# MainBoard.net
KiCad netlist of a schematic drawn in Altium Designer
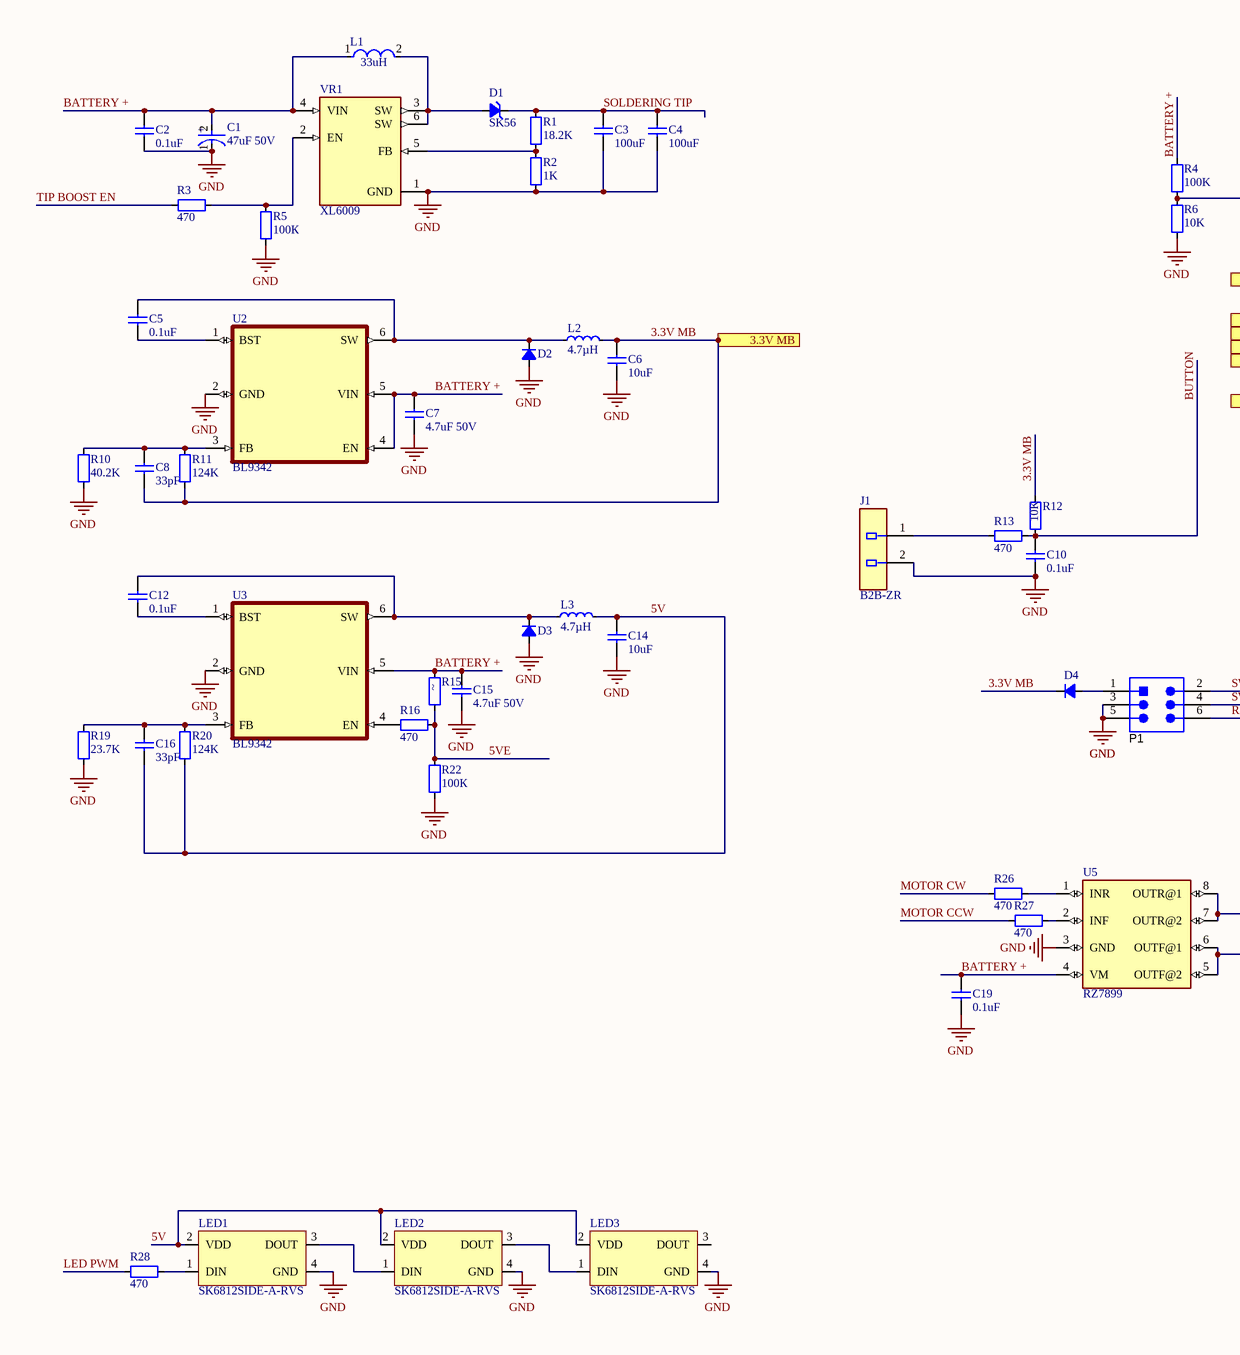
[diagram p0: MainBoard.SchDoc, left]
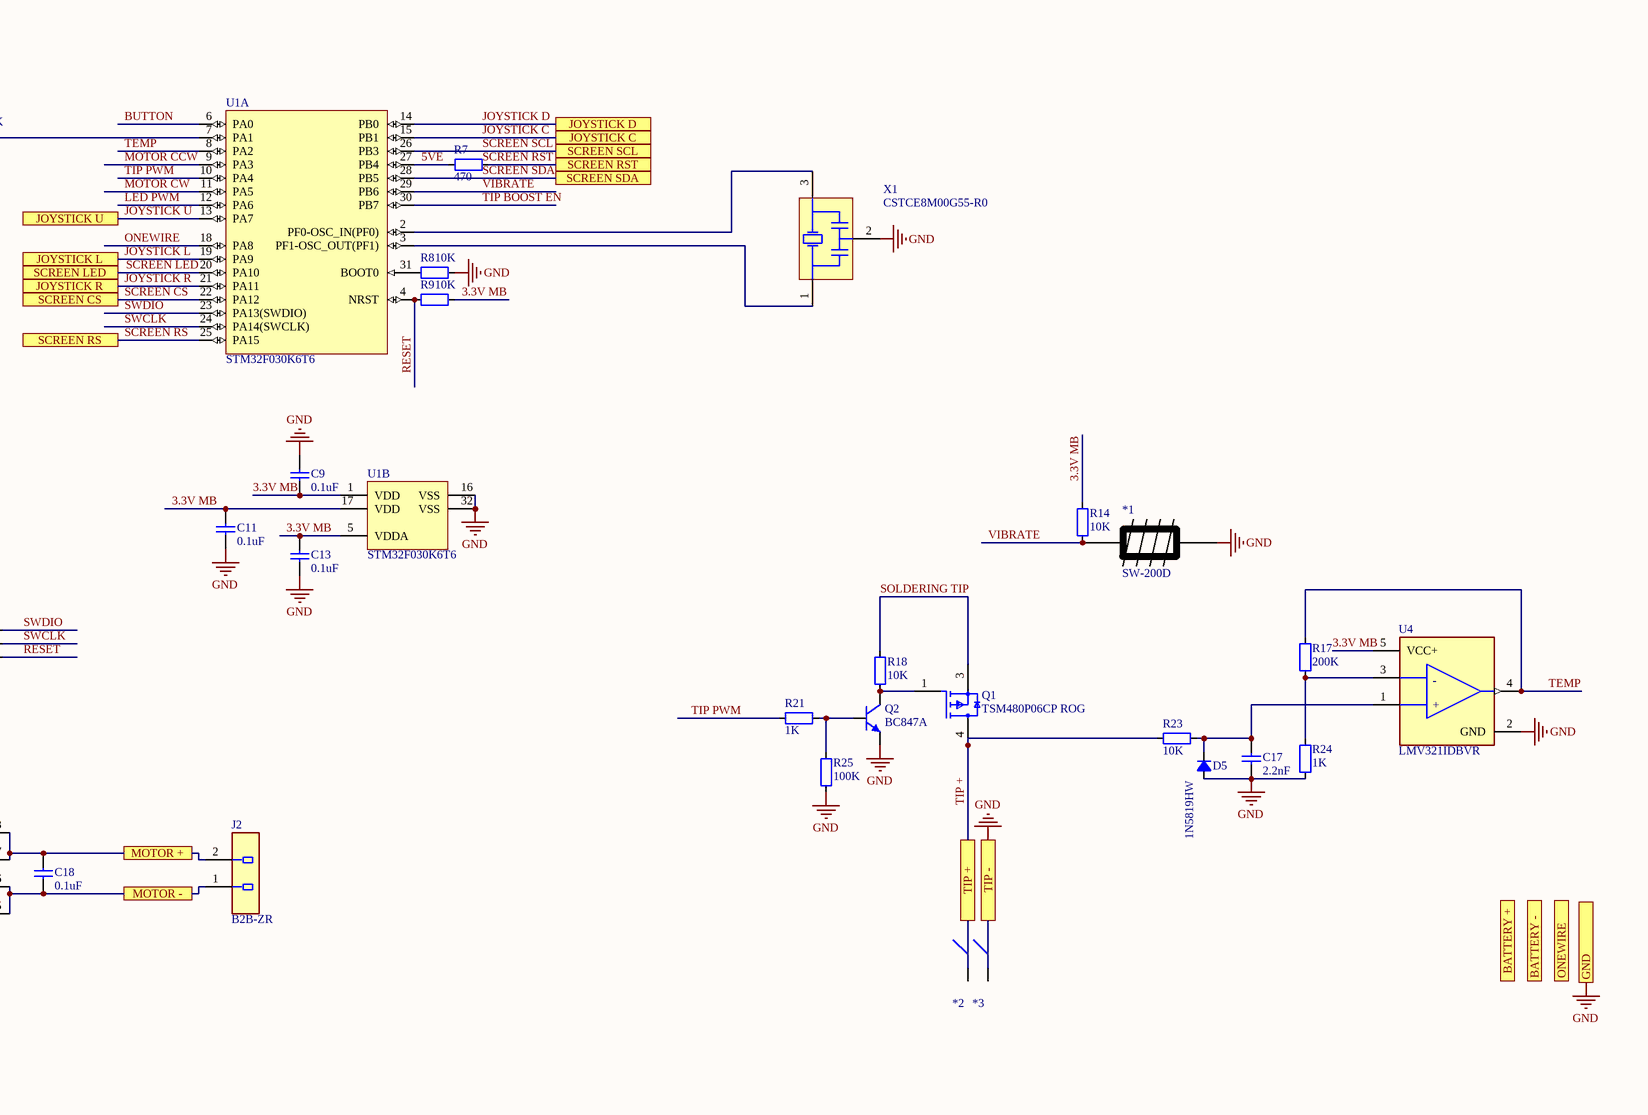
[diagram p1: MainBoard.SchDoc, right]

(export (version "E")
  (design (tool "Eeschema 10.0.6"))
  (components
    (comp (ref "*1")
      (value "SW-200D")
      (footprint "SW-200D")
      (libsource (lib "V_NB-IoT_3.1") (part "SW-200D"))
    )
    (comp (ref "*2") (value "Clipse") (footprint "CLIPSE") (libsource (lib "V_NB-IoT_3.1") (part "Clipse")))
    (comp (ref "*3") (value "Clipse") (footprint "CLIPSE") (libsource (lib "V_NB-IoT_3.1") (part "Clipse")))
    (comp (ref "C1")
      (value "47uF 50V")
      (footprint "FP-THV6.3X7.7-MFG")
      (fields (field (name "VOLTAGE") "50V") (field (name "TOLERANCE") "20%"))
      (libsource (lib "V_NB-IoT_3.1") (part "CAP ALUM SMD"))
    )
    (comp (ref "C2") (value "0.1uF") (footprint "1206") (libsource (lib "V_NB-IoT_3.1") (part "CAP")))
    (comp (ref "C3") (value "100uF") (footprint "C1210") (libsource (lib "V_NB-IoT_3.1") (part "CAP")))
    (comp (ref "C4") (value "100uF") (footprint "C1210") (libsource (lib "V_NB-IoT_3.1") (part "CAP")))
    (comp (ref "C5") (value "0.1uF") (footprint "R0603") (libsource (lib "V_NB-IoT_3.1") (part "CAP")))
    (comp (ref "C6") (value "10uF") (footprint "C0805") (libsource (lib "V_NB-IoT_3.1") (part "CAP")))
    (comp (ref "C7") (value "4.7uF 50V") (footprint "C0805") (libsource (lib "V_NB-IoT_3.1") (part "CAP")))
    (comp (ref "C8") (value "33pF") (footprint "R0603") (libsource (lib "V_NB-IoT_3.1") (part "CAP")))
    (comp (ref "C9") (value "0.1uF") (footprint "R0603") (libsource (lib "V_NB-IoT_3.1") (part "CAP")))
    (comp (ref "C10") (value "0.1uF") (footprint "R0603") (libsource (lib "V_NB-IoT_3.1") (part "CAP")))
    (comp (ref "C11") (value "0.1uF") (footprint "R0603") (libsource (lib "V_NB-IoT_3.1") (part "CAP")))
    (comp (ref "C12") (value "0.1uF") (footprint "R0603") (libsource (lib "V_NB-IoT_3.1") (part "CAP")))
    (comp (ref "C13") (value "0.1uF") (footprint "R0603") (libsource (lib "V_NB-IoT_3.1") (part "CAP")))
    (comp (ref "C14") (value "10uF") (footprint "C0805") (libsource (lib "V_NB-IoT_3.1") (part "CAP")))
    (comp (ref "C15") (value "4.7uF 50V") (footprint "C0805") (libsource (lib "V_NB-IoT_3.1") (part "CAP")))
    (comp (ref "C16") (value "33pF") (footprint "R0603") (libsource (lib "V_NB-IoT_3.1") (part "CAP")))
    (comp (ref "C17") (value "2.2nF") (footprint "R0603") (libsource (lib "V_NB-IoT_3.1") (part "CAP")))
    (comp (ref "C18") (value "0.1uF") (footprint "1206") (libsource (lib "V_NB-IoT_3.1") (part "CAP")))
    (comp (ref "C19") (value "0.1uF") (footprint "R0603") (libsource (lib "V_NB-IoT_3.1") (part "CAP")))
    (comp (ref "D1")
      (value "SK56")
      (footprint "DO-214AA(SMB)")
      (description "DO-214 Diode")
      (fields (field (name "MANUFACTURER PART NUMBER") "China"))
      (libsource (lib "V_NB-IoT_3.1") (part "DIODE_DO-214"))
    )
    (comp (ref "D2")
      (value "~")
      (footprint "SOD-123")
      (description "Schottky diode SOD123")
      (libsource (lib "V_NB-IoT_3.1") (part "Diode_SOD123"))
    )
    (comp (ref "D3")
      (value "~")
      (footprint "SOD-123")
      (description "Schottky diode SOD123")
      (libsource (lib "V_NB-IoT_3.1") (part "Diode_SOD123"))
    )
    (comp (ref "D4")
      (value "~")
      (footprint "SOD-123")
      (description "Schottky diode SOD123")
      (libsource (lib "V_NB-IoT_3.1") (part "Diode_SOD123"))
    )
    (comp (ref "D5")
      (value "1N5819HW")
      (footprint "SOD-123")
      (description "Schottky diode SOD123 1N5819HW")
      (libsource (lib "V_NB-IoT_3.1") (part "Diode_SOD123"))
    )
    (comp (ref "J1")
      (value "Conn_JST_B2B-ZR_eec")
      (footprint "JST_B2B-ZR_0")
      (description "CONN HEADER ZH TOP 2POS 1.5MM")
      (fields
        (field (name "MANUFACTURER") "JST")
        (field (name "DIGIKEY PART NUMBER") "455-1367-ND")
        (field (name "PART NUMBER") "B2B-ZR")
      )
      (libsource (lib "V_NB-IoT_3.1") (part "Conn_JST_B2B-ZR_eec"))
    )
    (comp (ref "J2")
      (value "Conn_JST_B2B-ZR_eec")
      (footprint "JST_B2B-ZR_0")
      (description "CONN HEADER ZH TOP 2POS 1.5MM")
      (fields
        (field (name "MANUFACTURER") "JST")
        (field (name "DIGIKEY PART NUMBER") "455-1367-ND")
        (field (name "PART NUMBER") "B2B-ZR")
      )
      (libsource (lib "") (part "Conn_JST_B2B-ZR_eec_1"))
    )
    (comp (ref "L1")
      (value "33uH")
      (footprint "IND_1040")
      (description "FIXED IND  1040 SMD")
      (fields (field (name "TOLERANCE") "20%") (field (name "MANUFACTURER") "Bourns"))
      (libsource (lib "V_NB-IoT_3.1") (part "IND_1040"))
    )
    (comp (ref "L2")
      (value "4.7µH")
      (footprint "INDC1608X06L")
      (description "Inductor, SMD")
      (fields
        (field (name "PART NUMBER") "L0603-10µ")
        (field (name "MANUFACTURER") "Taiyo Yuden")
        (field (name "PUBLISHER") "Nordic Semiconductor")
      )
      (libsource (lib "V_NB-IoT_3.1") (part "IND_1"))
    )
    (comp (ref "L3")
      (value "4.7µH")
      (footprint "INDC1608X06L")
      (description "Inductor, SMD")
      (fields
        (field (name "PART NUMBER") "L0603-10µ")
        (field (name "MANUFACTURER") "Taiyo Yuden")
        (field (name "PUBLISHER") "Nordic Semiconductor")
      )
      (libsource (lib "V_NB-IoT_3.1") (part "IND_1"))
    )
    (comp (ref "LED1")
      (value "SK6812SIDE-A-RVS")
      (footprint "SK6812SIDE-A-RVS")
      (description "2mA -40℃~+85℃ RGB SMD,2x4mm Light Emitting Diodes (LED) ROHS")
      (libsource (lib "V_NB-IoT_3.1") (part "SK6812SIDE-A-RVS"))
    )
    (comp (ref "LED2")
      (value "SK6812SIDE-A-RVS")
      (footprint "SK6812SIDE-A-RVS")
      (description "2mA -40℃~+85℃ RGB SMD,2x4mm Light Emitting Diodes (LED) ROHS")
      (libsource (lib "V_NB-IoT_3.1") (part "SK6812SIDE-A-RVS"))
    )
    (comp (ref "LED3")
      (value "SK6812SIDE-A-RVS")
      (footprint "SK6812SIDE-A-RVS")
      (description "2mA -40℃~+85℃ RGB SMD,2x4mm Light Emitting Diodes (LED) ROHS")
      (libsource (lib "V_NB-IoT_3.1") (part "SK6812SIDE-A-RVS"))
    )
    (comp (ref "P1")
      (value "TSW-103-07-G-D")
      (footprint "DS-1025-05 - 2x3")
      (fields (field (name "MANUFACTURER") "Samtec-Inc.") (field (name "MANUFACTURER_1") "Samtec"))
      (libsource (lib "V_NB-IoT_3.1") (part "DS-1025-05 - 2x3"))
    )
    (comp (ref "Q1")
      (value "TSM480P06CP ROG")
      (footprint "FP-TO-252-MFG")
      (description "MOSFET P-CHANNEL 60V 20A TO252")
      (libsource (lib "V_NB-IoT_3.1") (part "TSM480P06CP ROG"))
    )
    (comp (ref "Q2")
      (value "BC847A")
      (footprint "SOT95P237X112-3N")
      (description "NPN Silicon AF Transistor, 45 V VCEO, 100 mA IC, SOT23, Reel, Green")
      (fields (field (name "MANUFACTURER") "DIOTEC"))
      (libsource (lib "V_NB-IoT_3.1") (part "BC846A"))
    )
    (comp (ref "R1")
      (value "18.2K")
      (footprint "R0603")
      (description "Resistor SMD")
      (libsource (lib "V_NB-IoT_3.1") (part "RES SMD UNI"))
    )
    (comp (ref "R2")
      (value "1K")
      (footprint "R0603")
      (description "Resistor SMD")
      (libsource (lib "V_NB-IoT_3.1") (part "RES SMD UNI"))
    )
    (comp (ref "R3")
      (value "470")
      (footprint "R0603")
      (description "Resistor SMD")
      (libsource (lib "V_NB-IoT_3.1") (part "RES SMD UNI"))
    )
    (comp (ref "R4")
      (value "100K")
      (footprint "R0603")
      (description "Resistor SMD")
      (libsource (lib "V_NB-IoT_3.1") (part "RES SMD UNI"))
    )
    (comp (ref "R5")
      (value "100К")
      (footprint "R0603")
      (description "Resistor SMD")
      (libsource (lib "V_NB-IoT_3.1") (part "RES SMD UNI"))
    )
    (comp (ref "R6")
      (value "10K")
      (footprint "R0603")
      (description "Resistor SMD")
      (libsource (lib "V_NB-IoT_3.1") (part "RES SMD UNI"))
    )
    (comp (ref "R7")
      (value "470")
      (footprint "R0603")
      (description "Resistor SMD")
      (libsource (lib "V_NB-IoT_3.1") (part "RES SMD UNI"))
    )
    (comp (ref "R8")
      (value "10K")
      (footprint "R0603")
      (description "Resistor SMD")
      (libsource (lib "V_NB-IoT_3.1") (part "RES SMD UNI"))
    )
    (comp (ref "R9")
      (value "10K")
      (footprint "R0603")
      (description "Resistor SMD")
      (libsource (lib "V_NB-IoT_3.1") (part "RES SMD UNI"))
    )
    (comp (ref "R10")
      (value "40.2K")
      (footprint "R0603")
      (description "Resistor SMD")
      (libsource (lib "V_NB-IoT_3.1") (part "RES SMD UNI"))
    )
    (comp (ref "R11")
      (value "124K")
      (footprint "R0603")
      (description "Resistor SMD")
      (libsource (lib "V_NB-IoT_3.1") (part "RES SMD UNI"))
    )
    (comp (ref "R12")
      (value "10K")
      (footprint "R0603")
      (description "Resistor SMD")
      (libsource (lib "V_NB-IoT_3.1") (part "RES SMD UNI"))
    )
    (comp (ref "R13")
      (value "470")
      (footprint "R0603")
      (description "Resistor SMD")
      (libsource (lib "V_NB-IoT_3.1") (part "RES SMD UNI"))
    )
    (comp (ref "R14")
      (value "10K")
      (footprint "R0603")
      (description "Resistor SMD")
      (libsource (lib "V_NB-IoT_3.1") (part "RES SMD UNI"))
    )
    (comp (ref "R15")
      (value "~")
      (footprint "R0603")
      (description "Resistor SMD")
      (libsource (lib "V_NB-IoT_3.1") (part "RES SMD UNI"))
    )
    (comp (ref "R16")
      (value "470")
      (footprint "R0603")
      (description "Resistor SMD")
      (libsource (lib "V_NB-IoT_3.1") (part "RES SMD UNI"))
    )
    (comp (ref "R17")
      (value "200K")
      (footprint "R0603")
      (description "Resistor SMD")
      (libsource (lib "V_NB-IoT_3.1") (part "RES SMD UNI"))
    )
    (comp (ref "R18")
      (value "10K")
      (footprint "R0603")
      (description "Resistor SMD")
      (libsource (lib "V_NB-IoT_3.1") (part "RES SMD UNI"))
    )
    (comp (ref "R19")
      (value "23.7K")
      (footprint "R0603")
      (description "Resistor SMD")
      (libsource (lib "V_NB-IoT_3.1") (part "RES SMD UNI"))
    )
    (comp (ref "R20")
      (value "124K")
      (footprint "R0603")
      (description "Resistor SMD")
      (libsource (lib "V_NB-IoT_3.1") (part "RES SMD UNI"))
    )
    (comp (ref "R21")
      (value "1K")
      (footprint "R0603")
      (description "Resistor SMD")
      (libsource (lib "V_NB-IoT_3.1") (part "RES SMD UNI"))
    )
    (comp (ref "R22")
      (value "100К")
      (footprint "R0603")
      (description "Resistor SMD")
      (libsource (lib "V_NB-IoT_3.1") (part "RES SMD UNI"))
    )
    (comp (ref "R23")
      (value "10K")
      (footprint "R0603")
      (description "Resistor SMD")
      (libsource (lib "V_NB-IoT_3.1") (part "RES SMD UNI"))
    )
    (comp (ref "R24")
      (value "1K")
      (footprint "R0603")
      (description "Resistor SMD")
      (libsource (lib "V_NB-IoT_3.1") (part "RES SMD UNI"))
    )
    (comp (ref "R25")
      (value "100K")
      (footprint "R0603")
      (description "Resistor SMD")
      (libsource (lib "V_NB-IoT_3.1") (part "RES SMD UNI"))
    )
    (comp (ref "R26")
      (value "470")
      (footprint "R0603")
      (description "Resistor SMD")
      (libsource (lib "V_NB-IoT_3.1") (part "RES SMD UNI"))
    )
    (comp (ref "R27")
      (value "470")
      (footprint "R0603")
      (description "Resistor SMD")
      (libsource (lib "V_NB-IoT_3.1") (part "RES SMD UNI"))
    )
    (comp (ref "R28")
      (value "470")
      (footprint "R0603")
      (description "Resistor SMD")
      (libsource (lib "V_NB-IoT_3.1") (part "RES SMD UNI"))
    )
    (comp (ref "U1")
      (value "STM32F030K6T6")
      (footprint "LQFP32_L")
      (libsource (lib "V_NB-IoT_3.1") (part "CMP-0304-00020-2"))
    )
    (comp (ref "U2")
      (value "BL9342")
      (footprint "SOT23-6")
      (fields (field (name "MF") "{'manufacturer': u'Texas Instruments'}"))
      (libsource (lib "V_NB-IoT_3.1") (part "BL9342"))
    )
    (comp (ref "U3")
      (value "BL9342")
      (footprint "SOT23-6")
      (fields (field (name "MF") "{'manufacturer': u'Texas Instruments'}"))
      (libsource (lib "V_NB-IoT_3.1") (part "BL9342"))
    )
    (comp (ref "U4")
      (value "LMV321IDBVR")
      (footprint "FP-DBV0005A-MFG")
      (description "IC OPAMP GP 1 CIRCUIT SOT23-5")
      (fields
        (field (name "MANUFACTURER") "Texas Instruments")
        (field (name "OCTOPART") "https://octopart.com/lmv321idbvr-texas+instruments-410381")
      )
      (libsource (lib "V_NB-IoT_3.1") (part "LMV321"))
    )
    (comp (ref "U5")
      (value "RZ7899")
      (footprint "SOP-8_2-5R1S-IPC_B")
      (fields (field (name "MF") "{'manufacturer': u'Wuxi'}"))
      (libsource (lib "V_NB-IoT_3.1") (part "RZ7899"))
    )
    (comp (ref "VR1")
      (value "XL6009")
      (footprint "XL6009:DPAK170P1435X465-6N")
      (fields (field (name "MF") "{'manufacturer': u'XLSEMI'}"))
      (libsource (lib "V_NB-IoT_3.1") (part "XL6009"))
    )
    (comp (ref "X1")
      (value "CSTCE8M00G55-R0")
      (footprint "MURA-CSTCE_G_A-3_V")
      (description "Ceramic Resonator, 8 MHz, +/- 0.5%, -20 to 80 degC, 3-Pin SMD, RoHS, Tape and Reel")
      (fields (field (name "TOLERANCE") "0.5%") (field (name "MANUFACTURER") "Murata"))
      (libsource (lib "V_NB-IoT_3.1") (part "XTAL_SMD"))
    )
  )
  (nets
    (net (code "1") (name "/3.3V MB") (class "Default")
      (node (ref "C11") (pin "1") (pinfunction "1_1") (pintype "passive"))
      (node (ref "C13") (pin "1") (pinfunction "1_1") (pintype "passive"))
      (node (ref "C6") (pin "2") (pinfunction "2_2") (pintype "passive"))
      (node (ref "C8") (pin "1") (pinfunction "1_1") (pintype "passive"))
      (node (ref "C9") (pin "1") (pinfunction "1_1") (pintype "passive"))
      (node (ref "D4") (pin "2") (pinfunction "K_2") (pintype "passive"))
      (node (ref "L2") (pin "2") (pinfunction "2_2") (pintype "passive"))
      (node (ref "R11") (pin "1") (pinfunction "1_1") (pintype "passive"))
      (node (ref "R12") (pin "1") (pinfunction "1_1") (pintype "passive"))
      (node (ref "R14") (pin "2") (pinfunction "2_2") (pintype "passive"))
      (node (ref "R9") (pin "1") (pinfunction "1_1") (pintype "passive"))
      (node (ref "U1") (pin "1") (pinfunction "VDD_1") (pintype "power_in"))
      (node (ref "U1") (pin "17") (pinfunction "VDD_17") (pintype "power_in"))
      (node (ref "U1") (pin "5") (pinfunction "VDDA_5") (pintype "power_in"))
      (node (ref "U4") (pin "5") (pinfunction "VCC+_5") (pintype "power_in"))
    )
    (net (code "2") (name "/5V") (class "Default")
      (node (ref "C14") (pin "2") (pinfunction "2_2") (pintype "passive"))
      (node (ref "C16") (pin "1") (pinfunction "1_1") (pintype "passive"))
      (node (ref "L3") (pin "2") (pinfunction "2_2") (pintype "passive"))
      (node (ref "LED1") (pin "2") (pinfunction "VDD_2") (pintype "passive"))
      (node (ref "LED2") (pin "2") (pinfunction "VDD_2") (pintype "passive"))
      (node (ref "LED3") (pin "2") (pinfunction "VDD_2") (pintype "passive"))
      (node (ref "R20") (pin "1") (pinfunction "1_1") (pintype "passive"))
    )
    (net (code "3") (name "/5VE") (class "Default")
      (node (ref "R15") (pin "2") (pinfunction "2_2") (pintype "passive"))
      (node (ref "R16") (pin "1") (pinfunction "1_1") (pintype "passive"))
      (node (ref "R22") (pin "1") (pinfunction "1_1") (pintype "passive"))
      (node (ref "R7") (pin "2") (pinfunction "2_2") (pintype "passive"))
      (node (ref "U1") (pin "27") (pinfunction "PB4_27") (pintype "bidirectional"))
    )
    (net (code "4") (name "/BATTERY +") (class "Default")
      (node (ref "C1") (pin "2") (pinfunction "A_2") (pintype "passive"))
      (node (ref "C15") (pin "2") (pinfunction "2_2") (pintype "passive"))
      (node (ref "C19") (pin "1") (pinfunction "1_1") (pintype "passive"))
      (node (ref "C2") (pin "2") (pinfunction "2_2") (pintype "passive"))
      (node (ref "C7") (pin "2") (pinfunction "2_2") (pintype "passive"))
      (node (ref "L1") (pin "1") (pinfunction "1_1") (pintype "passive"))
      (node (ref "R15") (pin "1") (pinfunction "1_1") (pintype "passive"))
      (node (ref "R4") (pin "2") (pinfunction "2_2") (pintype "passive"))
      (node (ref "U2") (pin "4") (pinfunction "EN_4") (pintype "input"))
      (node (ref "U2") (pin "5") (pinfunction "VIN_5") (pintype "input"))
      (node (ref "U3") (pin "5") (pinfunction "VIN_5") (pintype "input"))
      (node (ref "U5") (pin "4") (pinfunction "VM_4") (pintype "bidirectional"))
      (node (ref "VR1") (pin "4") (pinfunction "VIN_4") (pintype "input"))
    )
    (net (code "6") (name "/BUTTON") (class "Default")
      (node (ref "C10") (pin "2") (pinfunction "2_2") (pintype "passive"))
      (node (ref "R12") (pin "2") (pinfunction "2_2") (pintype "passive"))
      (node (ref "R13") (pin "2") (pinfunction "2_2") (pintype "passive"))
      (node (ref "U1") (pin "6") (pinfunction "PA0_6") (pintype "bidirectional"))
    )
    (net (code "7") (name "/JOYSTICK D") (class "Default")
      (node (ref "U1") (pin "14") (pinfunction "PB0_14") (pintype "bidirectional"))
    )
    (net (code "8") (name "/JOYSTICK L") (class "Default")
      (node (ref "U1") (pin "19") (pinfunction "PA9_19") (pintype "bidirectional"))
    )
    (net (code "9") (name "/JOYSTICK R") (class "Default")
      (node (ref "U1") (pin "21") (pinfunction "PA11_21") (pintype "bidirectional"))
    )
    (net (code "10") (name "/JOYSTICK U") (class "Default")
      (node (ref "U1") (pin "13") (pinfunction "PA7_13") (pintype "bidirectional"))
    )
    (net (code "11") (name "/JOYSTICK С") (class "Default")
      (node (ref "U1") (pin "15") (pinfunction "PB1_15") (pintype "bidirectional"))
    )
    (net (code "12") (name "/LED PWM") (class "Default")
      (node (ref "R28") (pin "2") (pinfunction "2_2") (pintype "passive"))
      (node (ref "U1") (pin "12") (pinfunction "PA6_12") (pintype "bidirectional"))
    )
    (net (code "13") (name "/MOTOR +") (class "Default")
      (node (ref "C18") (pin "1") (pinfunction "1_1") (pintype "passive"))
      (node (ref "J2") (pin "2") (pinfunction "2_2") (pintype "passive"))
      (node (ref "U5") (pin "7") (pinfunction "OUTR@2_7") (pintype "bidirectional"))
      (node (ref "U5") (pin "8") (pinfunction "OUTR@1_8") (pintype "bidirectional"))
    )
    (net (code "14") (name "/MOTOR -") (class "Default")
      (node (ref "C18") (pin "2") (pinfunction "2_2") (pintype "passive"))
      (node (ref "J2") (pin "1") (pinfunction "1_1") (pintype "passive"))
      (node (ref "U5") (pin "5") (pinfunction "OUTF@2_5") (pintype "bidirectional"))
      (node (ref "U5") (pin "6") (pinfunction "OUTF@1_6") (pintype "bidirectional"))
    )
    (net (code "15") (name "/MOTOR CCW") (class "Default")
      (node (ref "R27") (pin "2") (pinfunction "2_2") (pintype "passive"))
      (node (ref "U1") (pin "9") (pinfunction "PA3_9") (pintype "bidirectional"))
    )
    (net (code "16") (name "/MOTOR CW") (class "Default")
      (node (ref "R26") (pin "2") (pinfunction "2_2") (pintype "passive"))
      (node (ref "U1") (pin "11") (pinfunction "PA5_11") (pintype "bidirectional"))
    )
    (net (code "17") (name "/ONEWIRE") (class "Default")
      (node (ref "U1") (pin "18") (pinfunction "PA8_18") (pintype "bidirectional"))
    )
    (net (code "18") (name "/RESET") (class "Default")
      (node (ref "P1") (pin "6") (pinfunction "6_6") (pintype "passive"))
      (node (ref "R9") (pin "2") (pinfunction "2_2") (pintype "passive"))
      (node (ref "U1") (pin "4") (pinfunction "NRST_4") (pintype "bidirectional"))
    )
    (net (code "19") (name "/SCREEN CS") (class "Default")
      (node (ref "U1") (pin "22") (pinfunction "PA12_22") (pintype "bidirectional"))
    )
    (net (code "20") (name "/SCREEN LED") (class "Default")
      (node (ref "U1") (pin "20") (pinfunction "PA10_20") (pintype "bidirectional"))
    )
    (net (code "21") (name "/SCREEN RS") (class "Default")
      (node (ref "U1") (pin "25") (pinfunction "PA15_25") (pintype "bidirectional"))
    )
    (net (code "22") (name "/SCREEN RST") (class "Default")
      (node (ref "R7") (pin "1") (pinfunction "1_1") (pintype "passive"))
    )
    (net (code "23") (name "/SCREEN SCL") (class "Default")
      (node (ref "U1") (pin "26") (pinfunction "PB3_26") (pintype "bidirectional"))
    )
    (net (code "24") (name "/SCREEN SDA") (class "Default")
      (node (ref "U1") (pin "28") (pinfunction "PB5_28") (pintype "bidirectional"))
    )
    (net (code "25") (name "/SOLDERING TIP") (class "Default")
      (node (ref "C3") (pin "2") (pinfunction "2_2") (pintype "passive"))
      (node (ref "C4") (pin "2") (pinfunction "2_2") (pintype "passive"))
      (node (ref "D1") (pin "1") (pinfunction "K_1") (pintype "passive"))
      (node (ref "Q1") (pin "3") (pinfunction "Source_3") (pintype "passive"))
      (node (ref "R1") (pin "1") (pinfunction "1_1") (pintype "passive"))
      (node (ref "R18") (pin "2") (pinfunction "2_2") (pintype "passive"))
    )
    (net (code "26") (name "/SWCLK") (class "Default")
      (node (ref "P1") (pin "4") (pinfunction "4_4") (pintype "passive"))
      (node (ref "U1") (pin "24") (pinfunction "PA14(SWCLK)_24") (pintype "bidirectional"))
    )
    (net (code "27") (name "/SWDIO") (class "Default")
      (node (ref "P1") (pin "2") (pinfunction "2_2") (pintype "passive"))
      (node (ref "U1") (pin "23") (pinfunction "PA13(SWDIO)_23") (pintype "bidirectional"))
    )
    (net (code "28") (name "/TEMP") (class "Default")
      (node (ref "R17") (pin "1") (pinfunction "1_1") (pintype "passive"))
      (node (ref "U1") (pin "8") (pinfunction "PA2_8") (pintype "bidirectional"))
      (node (ref "U4") (pin "4") (pinfunction "OUT_4") (pintype "output"))
    )
    (net (code "29") (name "/TIP +") (class "Default")
      (node (ref "*2") (pin "1") (pinfunction "1_1") (pintype "passive"))
      (node (ref "Q1") (pin "4") (pinfunction "Drain_4") (pintype "passive"))
      (node (ref "R23") (pin "1") (pinfunction "1_1") (pintype "passive"))
    )
    (net (code "30") (name "/TIP BOOST EN") (class "Default")
      (node (ref "R3") (pin "2") (pinfunction "2_2") (pintype "passive"))
      (node (ref "U1") (pin "30") (pinfunction "PB7_30") (pintype "bidirectional"))
    )
    (net (code "31") (name "/TIP PWM") (class "Default")
      (node (ref "R21") (pin "2") (pinfunction "2_2") (pintype "passive"))
      (node (ref "U1") (pin "10") (pinfunction "PA4_10") (pintype "bidirectional"))
    )
    (net (code "32") (name "/VIBRATE") (class "Default")
      (node (ref "*1") (pin "1") (pinfunction "1_1") (pintype "passive"))
      (node (ref "R14") (pin "1") (pinfunction "1_1") (pintype "passive"))
      (node (ref "U1") (pin "29") (pinfunction "PB6_29") (pintype "bidirectional"))
    )
    (net (code "33") (name "GND") (class "Default")
      (node (ref "*1") (pin "2") (pinfunction "2_2") (pintype "passive"))
      (node (ref "*3") (pin "1") (pinfunction "1_1") (pintype "passive"))
      (node (ref "C1") (pin "1") (pinfunction "C_1") (pintype "passive"))
      (node (ref "C10") (pin "1") (pinfunction "1_1") (pintype "passive"))
      (node (ref "C11") (pin "2") (pinfunction "2_2") (pintype "passive"))
      (node (ref "C13") (pin "2") (pinfunction "2_2") (pintype "passive"))
      (node (ref "C14") (pin "1") (pinfunction "1_1") (pintype "passive"))
      (node (ref "C15") (pin "1") (pinfunction "1_1") (pintype "passive"))
      (node (ref "C17") (pin "1") (pinfunction "1_1") (pintype "passive"))
      (node (ref "C19") (pin "2") (pinfunction "2_2") (pintype "passive"))
      (node (ref "C2") (pin "1") (pinfunction "1_1") (pintype "passive"))
      (node (ref "C3") (pin "1") (pinfunction "1_1") (pintype "passive"))
      (node (ref "C4") (pin "1") (pinfunction "1_1") (pintype "passive"))
      (node (ref "C6") (pin "1") (pinfunction "1_1") (pintype "passive"))
      (node (ref "C7") (pin "1") (pinfunction "1_1") (pintype "passive"))
      (node (ref "C9") (pin "2") (pinfunction "2_2") (pintype "passive"))
      (node (ref "D2") (pin "1") (pinfunction "A_1") (pintype "passive"))
      (node (ref "D3") (pin "1") (pinfunction "A_1") (pintype "passive"))
      (node (ref "D5") (pin "1") (pinfunction "A_1") (pintype "passive"))
      (node (ref "J1") (pin "2") (pinfunction "2_2") (pintype "passive"))
      (node (ref "LED1") (pin "4") (pinfunction "GND_4") (pintype "passive"))
      (node (ref "LED2") (pin "4") (pinfunction "GND_4") (pintype "passive"))
      (node (ref "LED3") (pin "4") (pinfunction "GND_4") (pintype "passive"))
      (node (ref "P1") (pin "3") (pinfunction "3_3") (pintype "passive"))
      (node (ref "P1") (pin "5") (pinfunction "5_5") (pintype "passive"))
      (node (ref "Q2") (pin "2") (pinfunction "E_2") (pintype "passive"))
      (node (ref "R10") (pin "1") (pinfunction "1_1") (pintype "passive"))
      (node (ref "R19") (pin "1") (pinfunction "1_1") (pintype "passive"))
      (node (ref "R2") (pin "2") (pinfunction "2_2") (pintype "passive"))
      (node (ref "R22") (pin "2") (pinfunction "2_2") (pintype "passive"))
      (node (ref "R24") (pin "2") (pinfunction "2_2") (pintype "passive"))
      (node (ref "R25") (pin "1") (pinfunction "1_1") (pintype "passive"))
      (node (ref "R5") (pin "2") (pinfunction "2_2") (pintype "passive"))
      (node (ref "R6") (pin "1") (pinfunction "1_1") (pintype "passive"))
      (node (ref "R8") (pin "1") (pinfunction "1_1") (pintype "passive"))
      (node (ref "U1") (pin "16") (pinfunction "VSS_16") (pintype "power_in"))
      (node (ref "U1") (pin "32") (pinfunction "VSS_32") (pintype "power_in"))
      (node (ref "U2") (pin "2") (pinfunction "GND_2") (pintype "bidirectional"))
      (node (ref "U3") (pin "2") (pinfunction "GND_2") (pintype "bidirectional"))
      (node (ref "U4") (pin "2") (pinfunction "GND_2") (pintype "power_in"))
      (node (ref "U5") (pin "3") (pinfunction "GND_3") (pintype "bidirectional"))
      (node (ref "VR1") (pin "1") (pinfunction "GND_1") (pintype "power_in"))
      (node (ref "X1") (pin "2") (pinfunction "GND_2") (pintype "power_in"))
    )
    (net (code "34") (name "Net-(D1-A)") (class "Default")
      (node (ref "D1") (pin "2") (pinfunction "A_2") (pintype "passive"))
      (node (ref "L1") (pin "2") (pinfunction "2_2") (pintype "passive"))
      (node (ref "VR1") (pin "3") (pinfunction "SW_3") (pintype "output"))
      (node (ref "VR1") (pin "6") (pinfunction "SW_6") (pintype "output"))
    )
    (net (code "35") (name "Net-(D2-K)") (class "Default")
      (node (ref "C5") (pin "2") (pinfunction "2_2") (pintype "passive"))
      (node (ref "D2") (pin "2") (pinfunction "K_2") (pintype "passive"))
      (node (ref "L2") (pin "1") (pinfunction "1_1") (pintype "passive"))
      (node (ref "U2") (pin "6") (pinfunction "SW_6") (pintype "output"))
    )
    (net (code "36") (name "Net-(D3-K)") (class "Default")
      (node (ref "C12") (pin "2") (pinfunction "2_2") (pintype "passive"))
      (node (ref "D3") (pin "2") (pinfunction "K_2") (pintype "passive"))
      (node (ref "L3") (pin "1") (pinfunction "1_1") (pintype "passive"))
      (node (ref "U3") (pin "6") (pinfunction "SW_6") (pintype "output"))
    )
    (net (code "37") (name "Net-(D4-A)") (class "Default")
      (node (ref "D4") (pin "1") (pinfunction "A_1") (pintype "passive"))
      (node (ref "P1") (pin "1") (pinfunction "1_1") (pintype "passive"))
    )
    (net (code "38") (name "Net-(D5-K)") (class "Default")
      (node (ref "C17") (pin "2") (pinfunction "2_2") (pintype "passive"))
      (node (ref "D5") (pin "2") (pinfunction "K_2") (pintype "passive"))
      (node (ref "R23") (pin "2") (pinfunction "2_2") (pintype "passive"))
      (node (ref "U4") (pin "1") (pinfunction "1IN+_1") (pintype "tri_state"))
    )
    (net (code "39") (name "Net-(J1-Pad1)") (class "Default")
      (node (ref "J1") (pin "1") (pinfunction "1_1") (pintype "passive"))
      (node (ref "R13") (pin "1") (pinfunction "1_1") (pintype "passive"))
    )
    (net (code "40") (name "Net-(LED1-DIN)") (class "Default")
      (node (ref "LED1") (pin "1") (pinfunction "DIN_1") (pintype "passive"))
      (node (ref "R28") (pin "1") (pinfunction "1_1") (pintype "passive"))
    )
    (net (code "41") (name "Net-(LED1-DOUT)") (class "Default")
      (node (ref "LED1") (pin "3") (pinfunction "DOUT_3") (pintype "passive"))
      (node (ref "LED2") (pin "1") (pinfunction "DIN_1") (pintype "passive"))
    )
    (net (code "42") (name "Net-(LED2-DOUT)") (class "Default")
      (node (ref "LED2") (pin "3") (pinfunction "DOUT_3") (pintype "passive"))
      (node (ref "LED3") (pin "1") (pinfunction "DIN_1") (pintype "passive"))
    )
    (net (code "43") (name "Net-(Q1-Gate)") (class "Default")
      (node (ref "Q1") (pin "1") (pinfunction "Gate_1") (pintype "passive"))
      (node (ref "Q2") (pin "3") (pinfunction "C_3") (pintype "passive"))
      (node (ref "R18") (pin "1") (pinfunction "1_1") (pintype "passive"))
    )
    (net (code "44") (name "Net-(Q2-B)") (class "Default")
      (node (ref "Q2") (pin "1") (pinfunction "B_1") (pintype "passive"))
      (node (ref "R21") (pin "1") (pinfunction "1_1") (pintype "passive"))
      (node (ref "R25") (pin "2") (pinfunction "2_2") (pintype "passive"))
    )
    (net (code "45") (name "Net-(U1A-BOOT0)") (class "Default")
      (node (ref "R8") (pin "2") (pinfunction "2_2") (pintype "passive"))
      (node (ref "U1") (pin "31") (pinfunction "BOOT0_31") (pintype "input"))
    )
    (net (code "46") (name "Net-(U1A-PA1)") (class "Default")
      (node (ref "R4") (pin "1") (pinfunction "1_1") (pintype "passive"))
      (node (ref "R6") (pin "2") (pinfunction "2_2") (pintype "passive"))
      (node (ref "U1") (pin "7") (pinfunction "PA1_7") (pintype "bidirectional"))
    )
    (net (code "47") (name "Net-(U1A-PF0-OSC_IN(PF0))") (class "Default")
      (node (ref "U1") (pin "2") (pinfunction "PF0-OSC_IN(PF0)_2") (pintype "bidirectional"))
      (node (ref "X1") (pin "3") (pinfunction "X2_3") (pintype "passive"))
    )
    (net (code "48") (name "Net-(U1A-PF1-OSC_OUT(PF1))") (class "Default")
      (node (ref "U1") (pin "3") (pinfunction "PF1-OSC_OUT(PF1)_3") (pintype "bidirectional"))
      (node (ref "X1") (pin "1") (pinfunction "X1_1") (pintype "passive"))
    )
    (net (code "49") (name "Net-(U2-BST)") (class "Default")
      (node (ref "C5") (pin "1") (pinfunction "1_1") (pintype "passive"))
      (node (ref "U2") (pin "1") (pinfunction "BST_1") (pintype "bidirectional"))
    )
    (net (code "50") (name "Net-(U2-FB)") (class "Default")
      (node (ref "C8") (pin "2") (pinfunction "2_2") (pintype "passive"))
      (node (ref "R10") (pin "2") (pinfunction "2_2") (pintype "passive"))
      (node (ref "R11") (pin "2") (pinfunction "2_2") (pintype "passive"))
      (node (ref "U2") (pin "3") (pinfunction "FB_3") (pintype "input"))
    )
    (net (code "51") (name "Net-(U3-BST)") (class "Default")
      (node (ref "C12") (pin "1") (pinfunction "1_1") (pintype "passive"))
      (node (ref "U3") (pin "1") (pinfunction "BST_1") (pintype "bidirectional"))
    )
    (net (code "52") (name "Net-(U3-EN)") (class "Default")
      (node (ref "R16") (pin "2") (pinfunction "2_2") (pintype "passive"))
      (node (ref "U3") (pin "4") (pinfunction "EN_4") (pintype "input"))
    )
    (net (code "53") (name "Net-(U3-FB)") (class "Default")
      (node (ref "C16") (pin "2") (pinfunction "2_2") (pintype "passive"))
      (node (ref "R19") (pin "2") (pinfunction "2_2") (pintype "passive"))
      (node (ref "R20") (pin "2") (pinfunction "2_2") (pintype "passive"))
      (node (ref "U3") (pin "3") (pinfunction "FB_3") (pintype "input"))
    )
    (net (code "54") (name "Net-(U4-1IN-)") (class "Default")
      (node (ref "R17") (pin "2") (pinfunction "2_2") (pintype "passive"))
      (node (ref "R24") (pin "1") (pinfunction "1_1") (pintype "passive"))
      (node (ref "U4") (pin "3") (pinfunction "1IN-_3") (pintype "tri_state"))
    )
    (net (code "55") (name "Net-(U5-INF)") (class "Default")
      (node (ref "R27") (pin "1") (pinfunction "1_1") (pintype "passive"))
      (node (ref "U5") (pin "2") (pinfunction "INF_2") (pintype "bidirectional"))
    )
    (net (code "56") (name "Net-(U5-INR)") (class "Default")
      (node (ref "R26") (pin "1") (pinfunction "1_1") (pintype "passive"))
      (node (ref "U5") (pin "1") (pinfunction "INR_1") (pintype "bidirectional"))
    )
    (net (code "57") (name "Net-(VR1-EN)") (class "Default")
      (node (ref "R3") (pin "1") (pinfunction "1_1") (pintype "passive"))
      (node (ref "R5") (pin "1") (pinfunction "1_1") (pintype "passive"))
      (node (ref "VR1") (pin "2") (pinfunction "EN_2") (pintype "input"))
    )
    (net (code "58") (name "Net-(VR1-FB)") (class "Default")
      (node (ref "R1") (pin "2") (pinfunction "2_2") (pintype "passive"))
      (node (ref "R2") (pin "1") (pinfunction "1_1") (pintype "passive"))
      (node (ref "VR1") (pin "5") (pinfunction "FB_5") (pintype "input"))
    )
    (net (code "59") (name "unconnected-(LED3-DOUT-Pad3)") (class "Default")
      (node (ref "LED3") (pin "3") (pinfunction "DOUT_3") (pintype "passive"))
    )
  )
)
